# RELAY7.net
KiCad netlist of a schematic drawn in Altium Designer
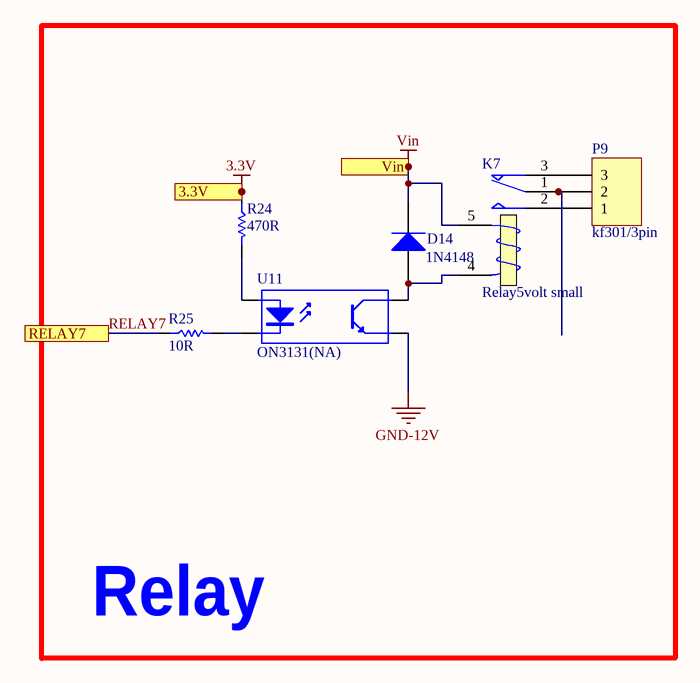
[diagram p0: RELAY7.SchDoc]

(export (version "E")
  (design (tool "Eeschema 10.0.6"))
  (components
    (comp (ref "D14")
      (value "1N4148")
      (footprint "sod123")
      (description "1 Amp General Purpose Rectifier")
      (fields (field (name "PUBLISHER") "Altium Limited"))
      (libsource (lib "Miscellaneous Devices") (part "Diode 1N4007"))
    )
    (comp (ref "K7")
      (value "Relay5volt small")
      (footprint "relay5_childern")
      (description "SPDT Relay")
      (fields (field (name "PUBLISHER") "Altium Limited"))
      (libsource (lib "FLIB") (part "Relay"))
    )
    (comp (ref "P9")
      (value "kf301/3pin")
      (footprint "Blue Connector 1*3 -kf301")
      (fields (field (name "PUBLISHER") "Altium Limited"))
      (libsource (lib "Miscellaneous Connectors") (part "Header 3"))
    )
    (comp (ref "R24")
      (value "470R")
      (footprint "0805/resistor")
      (description "Resistor")
      (fields (field (name "TOLERANCE") "5%") (field (name "POWER") "1/8 W"))
      (libsource (lib "skille") (part "Resistor"))
    )
    (comp (ref "R25")
      (value "10R")
      (footprint "0805/resistor")
      (description "Resistor")
      (fields (field (name "TOLERANCE") "5%") (field (name "POWER") "1/8 W"))
      (libsource (lib "skille") (part "Resistor"))
    )
    (comp (ref "U11")
      (value "ON3131(NA)")
      (footprint "OPTO_COUPLER")
      (description "4-Pin Phototransistor Optocoupler")
      (fields (field (name "PUBLISHER") "Altium Limited"))
      (libsource (lib "skille") (part "Optoisolator1"))
    )
  )
  (nets
    (net (code "1") (name "/RELAY7") (class "Default")
      (node (ref "R25") (pin "1") (pinfunction "1_1") (pintype "passive"))
    )
    (net (code "2") (name "3.3V") (class "Default")
      (node (ref "R24") (pin "1") (pinfunction "1_1") (pintype "passive"))
    )
    (net (code "3") (name "GND-12V") (class "Default")
      (node (ref "U11") (pin "3") (pinfunction "E_3") (pintype "passive"))
    )
    (net (code "4") (name "Net-(K7-COM)") (class "Default")
      (node (ref "K7") (pin "1") (pinfunction "COM_1") (pintype "passive"))
      (node (ref "P9") (pin "2") (pinfunction "2_2") (pintype "passive"))
    )
    (net (code "5") (name "Net-(K7-NO)") (class "Default")
      (node (ref "K7") (pin "2") (pinfunction "NO_2") (pintype "passive"))
      (node (ref "P9") (pin "1") (pinfunction "1_1") (pintype "passive"))
    )
    (net (code "6") (name "Net-(K7-T1)") (class "Default")
      (node (ref "K7") (pin "3") (pinfunction "T1_3") (pintype "passive"))
      (node (ref "P9") (pin "3") (pinfunction "3_3") (pintype "passive"))
    )
    (net (code "7") (name "Net-(K7-T2)") (class "Default")
      (node (ref "D14") (pin "A") (pinfunction "A_A") (pintype "passive"))
      (node (ref "K7") (pin "4") (pinfunction "T2_4") (pintype "passive"))
      (node (ref "U11") (pin "4") (pinfunction "C_4") (pintype "passive"))
    )
    (net (code "8") (name "Net-(U11-A)") (class "Default")
      (node (ref "R24") (pin "2") (pinfunction "2_2") (pintype "passive"))
      (node (ref "U11") (pin "1") (pinfunction "A_1") (pintype "passive"))
    )
    (net (code "9") (name "Net-(U11-K)") (class "Default")
      (node (ref "R25") (pin "2") (pinfunction "2_2") (pintype "passive"))
      (node (ref "U11") (pin "2") (pinfunction "K_2") (pintype "passive"))
    )
    (net (code "10") (name "Vin") (class "Default")
      (node (ref "D14") (pin "K") (pinfunction "K_K") (pintype "passive"))
      (node (ref "K7") (pin "5") (pinfunction "5_5") (pintype "passive"))
    )
  )
)
